# controller.net
KiCad netlist of a schematic drawn in EAGLE
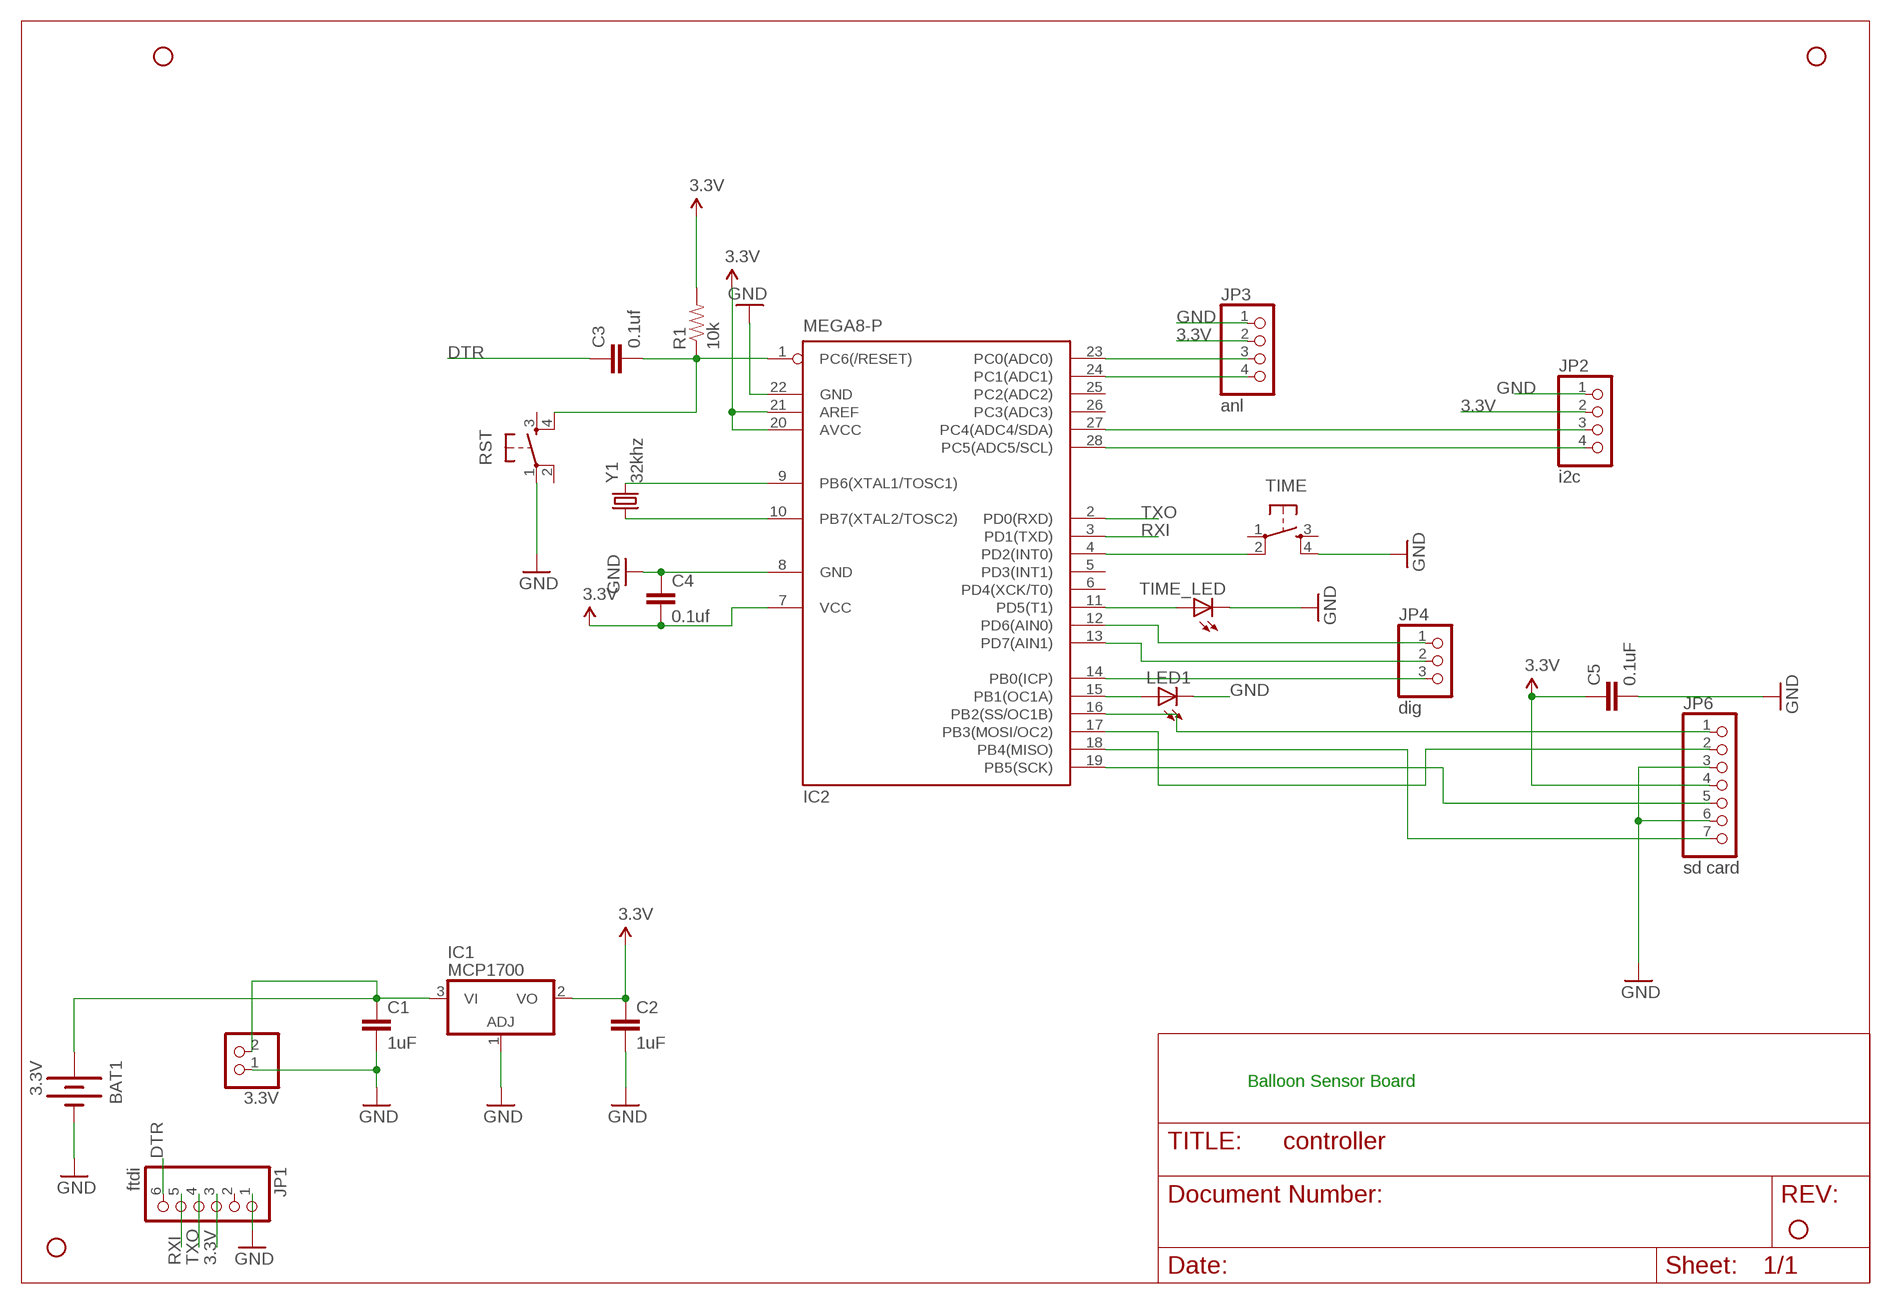
[diagram p0: schematic, sheet 1]

(export (version "E")
  (design (tool "Eeschema 10.0.6"))
  (components
    (comp (ref "3.3V")
      (value "PINHD-1X2")
      (footprint "eagle-import:1X02")
      (libsource (lib "eagle-import") (part "PINHD-1X2"))
    )
    (comp (ref "BAT1")
      (value "3.3V")
      (footprint "eagle-import:BATTCON_245MM")
      (libsource (lib "eagle-import") (part "BATTERY245MM"))
    )
    (comp (ref "C1")
      (value "1uF")
      (footprint "eagle-import:CAP-PTH-5MM")
      (libsource (lib "eagle-import") (part "CAPPTH1"))
    )
    (comp (ref "C2")
      (value "1uF")
      (footprint "eagle-import:CAP-PTH-5MM")
      (libsource (lib "eagle-import") (part "CAPPTH1"))
    )
    (comp (ref "C3")
      (value "0.1uf")
      (footprint "eagle-import:CAP-PTH-5MM")
      (libsource (lib "eagle-import") (part "CAPPTH1"))
    )
    (comp (ref "C4")
      (value "0.1uf")
      (footprint "eagle-import:CAP-PTH-5MM")
      (libsource (lib "eagle-import") (part "CAPPTH1"))
    )
    (comp (ref "C5")
      (value "0.1uF")
      (footprint "eagle-import:CAP-PTH-5MM")
      (libsource (lib "eagle-import") (part "CAPPTH1"))
    )
    (comp (ref "IC1")
      (value "MCP1700")
      (footprint "eagle-import:TO92")
      (libsource (lib "eagle-import") (part "317LZLM"))
    )
    (comp (ref "IC2")
      (value "MEGA8-P")
      (footprint "eagle-import:DIL28-3")
      (libsource (lib "eagle-import") (part "MEGA8-P"))
    )
    (comp (ref "JP1")
      (value "ftdi")
      (footprint "eagle-import:1X06")
      (libsource (lib "eagle-import") (part "PINHD-1X6"))
    )
    (comp (ref "JP2")
      (value "i2c")
      (footprint "eagle-import:1X04")
      (libsource (lib "eagle-import") (part "PINHD-1X4"))
    )
    (comp (ref "JP3")
      (value "anl")
      (footprint "eagle-import:1X04")
      (libsource (lib "eagle-import") (part "PINHD-1X4"))
    )
    (comp (ref "JP4")
      (value "dig")
      (footprint "eagle-import:1X03")
      (libsource (lib "eagle-import") (part "PINHD-1X3"))
    )
    (comp (ref "JP6")
      (value "sd card")
      (footprint "eagle-import:1X07")
      (libsource (lib "eagle-import") (part "PINHD-1X7"))
    )
    (comp (ref "LED1")
      (value "LED5MM")
      (footprint "eagle-import:LED5MM")
      (libsource (lib "eagle-import") (part "LED5MM"))
    )
    (comp (ref "R1")
      (value "10k")
      (footprint "eagle-import:AXIAL-0.5")
      (libsource (lib "eagle-import") (part "RESISTORPTH-1/2W"))
    )
    (comp (ref "RST")
      (value "TAC_SWITCHPTH")
      (footprint "eagle-import:TACTILE-PTH")
      (libsource (lib "eagle-import") (part "TAC_SWITCHPTH"))
    )
    (comp (ref "STANDOFF1")
      (value "STAND-OFF")
      (footprint "eagle-import:STAND-OFF")
      (libsource (lib "eagle-import") (part "STAND-OFF"))
    )
    (comp (ref "STANDOFF2")
      (value "STAND-OFF")
      (footprint "eagle-import:STAND-OFF")
      (libsource (lib "eagle-import") (part "STAND-OFF"))
    )
    (comp (ref "STANDOFF3")
      (value "STAND-OFF")
      (footprint "eagle-import:STAND-OFF")
      (libsource (lib "eagle-import") (part "STAND-OFF"))
    )
    (comp (ref "STANDOFF4")
      (value "STAND-OFF")
      (footprint "eagle-import:STAND-OFF")
      (libsource (lib "eagle-import") (part "STAND-OFF"))
    )
    (comp (ref "TIME")
      (value "TAC_SWITCHPTH")
      (footprint "eagle-import:TACTILE-PTH")
      (libsource (lib "eagle-import") (part "TAC_SWITCHPTH"))
    )
    (comp (ref "TIME_LED")
      (value "LED5MM")
      (footprint "eagle-import:LED5MM")
      (libsource (lib "eagle-import") (part "LED5MM"))
    )
    (comp (ref "Y1")
      (value "32khz")
      (footprint "eagle-import:TC26H")
      (libsource (lib "eagle-import") (part "CRYSTALTC26H"))
    )
  )
  (nets
    (net (code "1") (name "/DTR") (class "Default")
      (node (ref "C3") (pin "1") (pinfunction "1_1") (pintype "passive"))
      (node (ref "JP1") (pin "6") (pinfunction "6_6") (pintype "passive"))
    )
    (net (code "2") (name "/RXI") (class "Default")
      (node (ref "IC2") (pin "3") (pinfunction "PD1(TXD)_3") (pintype "bidirectional"))
      (node (ref "JP1") (pin "5") (pinfunction "5_5") (pintype "passive"))
    )
    (net (code "3") (name "/TXO") (class "Default")
      (node (ref "IC2") (pin "2") (pinfunction "PD0(RXD)_2") (pintype "bidirectional"))
      (node (ref "JP1") (pin "4") (pinfunction "4_4") (pintype "passive"))
    )
    (net (code "4") (name "3.3V") (class "Default")
      (node (ref "C2") (pin "1") (pinfunction "1_1") (pintype "passive"))
      (node (ref "C4") (pin "2") (pinfunction "2_2") (pintype "passive"))
      (node (ref "C5") (pin "1") (pinfunction "1_1") (pintype "passive"))
      (node (ref "IC1") (pin "2") (pinfunction "VO_2") (pintype "passive"))
      (node (ref "IC2") (pin "20") (pinfunction "AVCC_20") (pintype "power_in"))
      (node (ref "IC2") (pin "21") (pinfunction "AREF_21") (pintype "passive"))
      (node (ref "IC2") (pin "7") (pinfunction "VCC_7") (pintype "power_in"))
      (node (ref "JP1") (pin "3") (pinfunction "3_3") (pintype "passive"))
      (node (ref "JP2") (pin "2") (pinfunction "2_2") (pintype "passive"))
      (node (ref "JP3") (pin "2") (pinfunction "2_2") (pintype "passive"))
      (node (ref "JP6") (pin "4") (pinfunction "4_4") (pintype "passive"))
      (node (ref "R1") (pin "P$2") (pinfunction "2_P$2") (pintype "passive"))
    )
    (net (code "5") (name "GND") (class "Default")
      (node (ref "3.3V") (pin "1") (pinfunction "1_1") (pintype "passive"))
      (node (ref "BAT1") (pin "2") (pinfunction "-_2") (pintype "power_in"))
      (node (ref "C1") (pin "2") (pinfunction "2_2") (pintype "passive"))
      (node (ref "C2") (pin "2") (pinfunction "2_2") (pintype "passive"))
      (node (ref "C4") (pin "1") (pinfunction "1_1") (pintype "passive"))
      (node (ref "C5") (pin "2") (pinfunction "2_2") (pintype "passive"))
      (node (ref "IC1") (pin "1") (pinfunction "ADJ_1") (pintype "input"))
      (node (ref "IC2") (pin "22") (pinfunction "GND_22") (pintype "power_in"))
      (node (ref "IC2") (pin "8") (pinfunction "GND_8") (pintype "power_in"))
      (node (ref "JP1") (pin "1") (pinfunction "1_1") (pintype "passive"))
      (node (ref "JP2") (pin "1") (pinfunction "1_1") (pintype "passive"))
      (node (ref "JP3") (pin "1") (pinfunction "1_1") (pintype "passive"))
      (node (ref "JP6") (pin "3") (pinfunction "3_3") (pintype "passive"))
      (node (ref "JP6") (pin "6") (pinfunction "6_6") (pintype "passive"))
      (node (ref "LED1") (pin "K") (pinfunction "C_K") (pintype "passive"))
      (node (ref "RST") (pin "1") (pinfunction "1_1") (pintype "passive"))
      (node (ref "TIME") (pin "4") (pinfunction "4_4") (pintype "passive"))
      (node (ref "TIME_LED") (pin "K") (pinfunction "C_K") (pintype "passive"))
    )
    (net (code "6") (name "Net-(BAT1-+)") (class "Default")
      (node (ref "3.3V") (pin "2") (pinfunction "2_2") (pintype "passive"))
      (node (ref "BAT1") (pin "1") (pinfunction "+_1") (pintype "power_in"))
      (node (ref "C1") (pin "1") (pinfunction "1_1") (pintype "passive"))
      (node (ref "IC1") (pin "3") (pinfunction "VI_3") (pintype "input"))
    )
    (net (code "7") (name "Net-(IC2-PB0(ICP))") (class "Default")
      (node (ref "IC2") (pin "14") (pinfunction "PB0(ICP)_14") (pintype "bidirectional"))
      (node (ref "JP4") (pin "3") (pinfunction "3_3") (pintype "passive"))
    )
    (net (code "8") (name "Net-(IC2-PB1(OC1A))") (class "Default")
      (node (ref "IC2") (pin "15") (pinfunction "PB1(OC1A)_15") (pintype "bidirectional"))
      (node (ref "LED1") (pin "A") (pinfunction "A_A") (pintype "passive"))
    )
    (net (code "9") (name "Net-(IC2-PB2(SS{slash}OC1B))") (class "Default")
      (node (ref "IC2") (pin "16") (pinfunction "PB2(SS/OC1B)_16") (pintype "bidirectional"))
      (node (ref "JP6") (pin "1") (pinfunction "1_1") (pintype "passive"))
    )
    (net (code "10") (name "Net-(IC2-PB3(MOSI{slash}OC2))") (class "Default")
      (node (ref "IC2") (pin "17") (pinfunction "PB3(MOSI/OC2)_17") (pintype "bidirectional"))
      (node (ref "JP6") (pin "2") (pinfunction "2_2") (pintype "passive"))
    )
    (net (code "11") (name "Net-(IC2-PB4(MISO))") (class "Default")
      (node (ref "IC2") (pin "18") (pinfunction "PB4(MISO)_18") (pintype "bidirectional"))
      (node (ref "JP6") (pin "7") (pinfunction "7_7") (pintype "passive"))
    )
    (net (code "12") (name "Net-(IC2-PB5(SCK))") (class "Default")
      (node (ref "IC2") (pin "19") (pinfunction "PB5(SCK)_19") (pintype "bidirectional"))
      (node (ref "JP6") (pin "5") (pinfunction "5_5") (pintype "passive"))
    )
    (net (code "13") (name "Net-(IC2-PB6(XTAL1{slash}TOSC1))") (class "Default")
      (node (ref "IC2") (pin "9") (pinfunction "PB6(XTAL1/TOSC1)_9") (pintype "bidirectional"))
      (node (ref "Y1") (pin "2") (pinfunction "2_2") (pintype "passive"))
    )
    (net (code "14") (name "Net-(IC2-PB7(XTAL2{slash}TOSC2))") (class "Default")
      (node (ref "IC2") (pin "10") (pinfunction "PB7(XTAL2/TOSC2)_10") (pintype "bidirectional"))
      (node (ref "Y1") (pin "1") (pinfunction "1_1") (pintype "passive"))
    )
    (net (code "15") (name "Net-(IC2-PC0(ADC0))") (class "Default")
      (node (ref "IC2") (pin "23") (pinfunction "PC0(ADC0)_23") (pintype "bidirectional"))
      (node (ref "JP3") (pin "3") (pinfunction "3_3") (pintype "passive"))
    )
    (net (code "16") (name "Net-(IC2-PC1(ADC1))") (class "Default")
      (node (ref "IC2") (pin "24") (pinfunction "PC1(ADC1)_24") (pintype "bidirectional"))
      (node (ref "JP3") (pin "4") (pinfunction "4_4") (pintype "passive"))
    )
    (net (code "17") (name "Net-(IC2-PC4(ADC4{slash}SDA))") (class "Default")
      (node (ref "IC2") (pin "27") (pinfunction "PC4(ADC4/SDA)_27") (pintype "bidirectional"))
      (node (ref "JP2") (pin "3") (pinfunction "3_3") (pintype "passive"))
    )
    (net (code "18") (name "Net-(IC2-PC5(ADC5{slash}SCL))") (class "Default")
      (node (ref "IC2") (pin "28") (pinfunction "PC5(ADC5/SCL)_28") (pintype "bidirectional"))
      (node (ref "JP2") (pin "4") (pinfunction "4_4") (pintype "passive"))
    )
    (net (code "19") (name "Net-(IC2-PC6({slash}RESET))") (class "Default")
      (node (ref "C3") (pin "2") (pinfunction "2_2") (pintype "passive"))
      (node (ref "IC2") (pin "1") (pinfunction "PC6(/RESET)_1") (pintype "bidirectional"))
      (node (ref "R1") (pin "P$1") (pinfunction "1_P$1") (pintype "passive"))
      (node (ref "RST") (pin "4") (pinfunction "4_4") (pintype "passive"))
    )
    (net (code "20") (name "Net-(IC2-PD2(INT0))") (class "Default")
      (node (ref "IC2") (pin "4") (pinfunction "PD2(INT0)_4") (pintype "bidirectional"))
      (node (ref "TIME") (pin "2") (pinfunction "2_2") (pintype "passive"))
    )
    (net (code "21") (name "Net-(IC2-PD5(T1))") (class "Default")
      (node (ref "IC2") (pin "11") (pinfunction "PD5(T1)_11") (pintype "bidirectional"))
      (node (ref "TIME_LED") (pin "A") (pinfunction "A_A") (pintype "passive"))
    )
    (net (code "22") (name "Net-(IC2-PD6(AIN0))") (class "Default")
      (node (ref "IC2") (pin "12") (pinfunction "PD6(AIN0)_12") (pintype "bidirectional"))
      (node (ref "JP4") (pin "1") (pinfunction "1_1") (pintype "passive"))
    )
    (net (code "23") (name "Net-(IC2-PD7(AIN1))") (class "Default")
      (node (ref "IC2") (pin "13") (pinfunction "PD7(AIN1)_13") (pintype "bidirectional"))
      (node (ref "JP4") (pin "2") (pinfunction "2_2") (pintype "passive"))
    )
    (net (code "24") (name "unconnected-(IC2-PC2(ADC2)-Pad25)") (class "Default")
      (node (ref "IC2") (pin "25") (pinfunction "PC2(ADC2)_25") (pintype "bidirectional"))
    )
    (net (code "25") (name "unconnected-(IC2-PC3(ADC3)-Pad26)") (class "Default")
      (node (ref "IC2") (pin "26") (pinfunction "PC3(ADC3)_26") (pintype "bidirectional"))
    )
    (net (code "26") (name "unconnected-(IC2-PD3(INT1)-Pad5)") (class "Default")
      (node (ref "IC2") (pin "5") (pinfunction "PD3(INT1)_5") (pintype "bidirectional"))
    )
    (net (code "27") (name "unconnected-(IC2-PD4(XCK{slash}T0)-Pad6)") (class "Default")
      (node (ref "IC2") (pin "6") (pinfunction "PD4(XCK/T0)_6") (pintype "bidirectional"))
    )
    (net (code "28") (name "unconnected-(JP1-Pad2)") (class "Default")
      (node (ref "JP1") (pin "2") (pinfunction "2_2") (pintype "passive"))
    )
    (net (code "29") (name "unconnected-(RST-Pad2)") (class "Default")
      (node (ref "RST") (pin "2") (pinfunction "2_2") (pintype "passive"))
    )
    (net (code "30") (name "unconnected-(RST-Pad3)") (class "Default")
      (node (ref "RST") (pin "3") (pinfunction "3_3") (pintype "passive"))
    )
    (net (code "31") (name "unconnected-(TIME-Pad1)") (class "Default")
      (node (ref "TIME") (pin "1") (pinfunction "1_1") (pintype "passive"))
    )
    (net (code "32") (name "unconnected-(TIME-Pad3)") (class "Default")
      (node (ref "TIME") (pin "3") (pinfunction "3_3") (pintype "passive"))
    )
  )
)
